# RF_Driver.net
KiCad netlist of a schematic drawn in Altium Designer
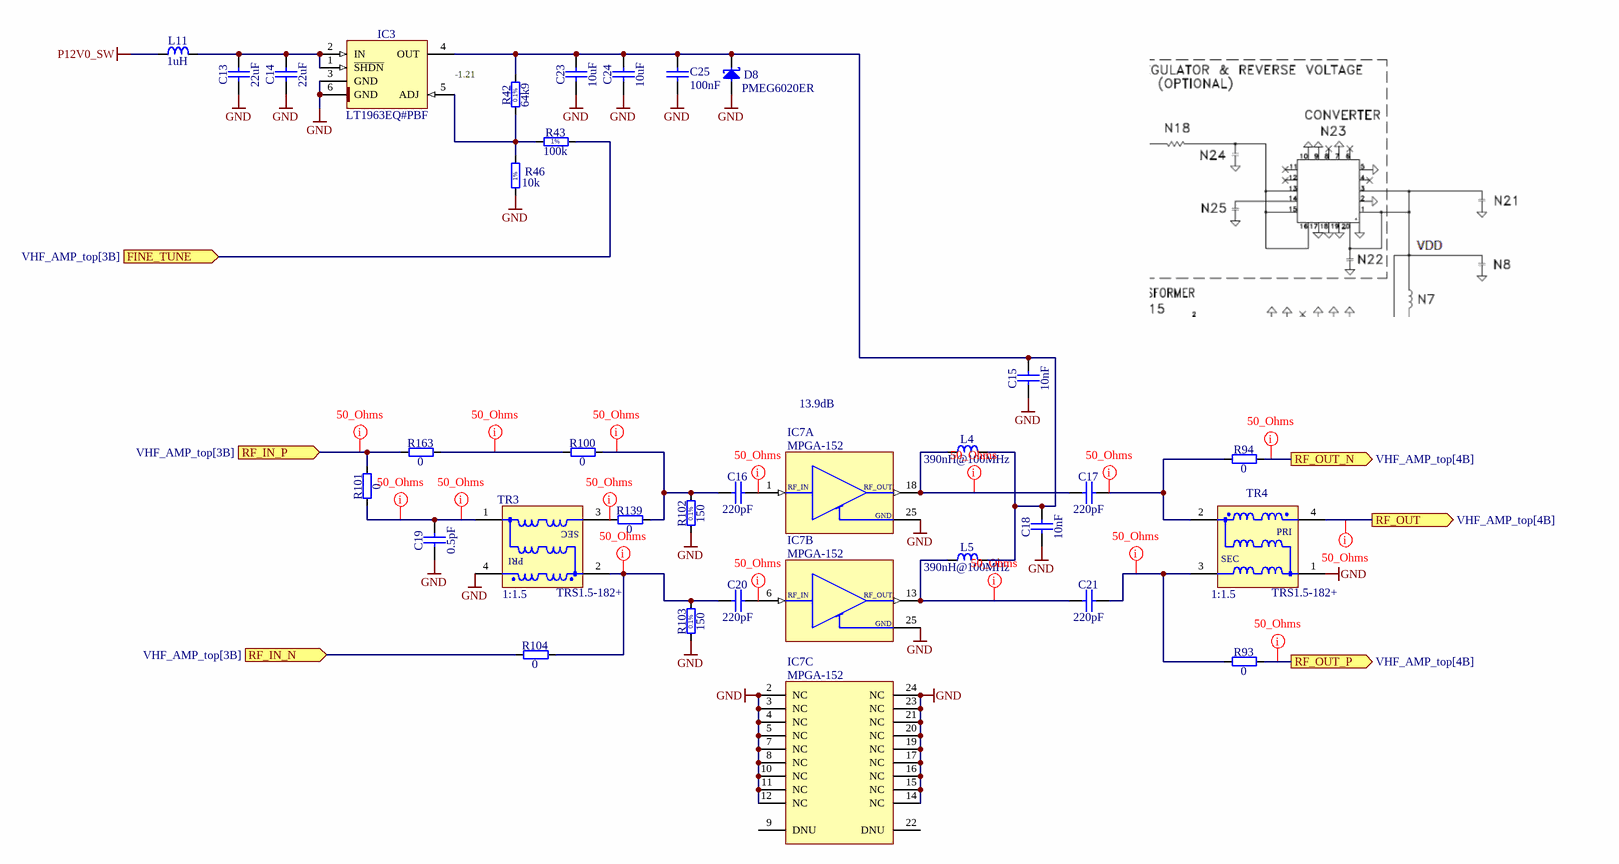
[diagram p0: RF_Driver.SchDoc]

(export (version "E")
  (design (tool "Eeschema 10.0.6"))
  (components
    (comp (ref "C13")
      (value "22uF")
      (footprint "CAPC3225X140N")
      (description "Non-polarised capacitor")
      (fields
        (field (name "PART NUMBER") "CC1210_22UF_25V_20%_X7R")
        (field (name "VOLTAGE") "25V")
        (field (name "AUTHOR") "CERN DEM JLC")
      )
      (libsource (lib "Capacitors") (part "Capacitor - non polarized"))
    )
    (comp (ref "C14")
      (value "22uF")
      (footprint "CAPC3225X140N")
      (description "Non-polarised capacitor")
      (fields
        (field (name "PART NUMBER") "CC1210_22UF_25V_20%_X7R")
        (field (name "VOLTAGE") "25V")
        (field (name "AUTHOR") "CERN DEM JLC")
      )
      (libsource (lib "Capacitors") (part "Capacitor - non polarized"))
    )
    (comp (ref "C15")
      (value "10nF")
      (footprint "CAPC1005X55N")
      (description "Non-polarised capacitor")
      (fields
        (field (name "PART NUMBER") "CC0402_10NF_16V_10%_X7R")
        (field (name "VOLTAGE") "16V")
        (field (name "AUTHOR") "CERN DEM JLC")
      )
      (libsource (lib "Capacitors") (part "Capacitor - non polarized"))
    )
    (comp (ref "C16")
      (value "220pF")
      (footprint "CAPC1005X55N")
      (description "Non-polarised capacitor")
      (fields
        (field (name "PART NUMBER") "CC0402_220PF_50V_5%_C0G")
        (field (name "VOLTAGE") "50V")
        (field (name "AUTHOR") "CERN DEM JLC")
      )
      (libsource (lib "Capacitors") (part "Capacitor - non polarized"))
    )
    (comp (ref "C17")
      (value "220pF")
      (footprint "CAPC1005X55N")
      (description "Non-polarised capacitor")
      (fields
        (field (name "PART NUMBER") "CC0402_220PF_50V_5%_C0G")
        (field (name "VOLTAGE") "50V")
        (field (name "AUTHOR") "CERN DEM JLC")
      )
      (libsource (lib "Capacitors") (part "Capacitor - non polarized"))
    )
    (comp (ref "C18")
      (value "10nF")
      (footprint "CAPC1005X55N")
      (description "Non-polarised capacitor")
      (fields
        (field (name "PART NUMBER") "CC0402_10NF_16V_10%_X7R")
        (field (name "VOLTAGE") "16V")
        (field (name "AUTHOR") "CERN DEM JLC")
      )
      (libsource (lib "Capacitors") (part "Capacitor - non polarized"))
    )
    (comp (ref "C19")
      (value "0.5pF")
      (footprint "CAPC1005X50N")
      (description "Non-polarised capacitor")
      (fields
        (field (name "PART NUMBER") "CC0402_0.5PF_25V_0.05PF_AVX_04023J0R5ABSTR")
        (field (name "VOLTAGE") "25V")
        (field (name "AUTHOR") "CERN DEM JLC")
      )
      (libsource (lib "Capacitors") (part "Capacitor - non polarized"))
    )
    (comp (ref "C20")
      (value "220pF")
      (footprint "CAPC1005X55N")
      (description "Non-polarised capacitor")
      (fields
        (field (name "PART NUMBER") "CC0402_220PF_50V_5%_C0G")
        (field (name "VOLTAGE") "50V")
        (field (name "AUTHOR") "CERN DEM JLC")
      )
      (libsource (lib "Capacitors") (part "Capacitor - non polarized"))
    )
    (comp (ref "C21")
      (value "220pF")
      (footprint "CAPC1005X55N")
      (description "Non-polarised capacitor")
      (fields
        (field (name "PART NUMBER") "CC0402_220PF_50V_5%_C0G")
        (field (name "VOLTAGE") "50V")
        (field (name "AUTHOR") "CERN DEM JLC")
      )
      (libsource (lib "Capacitors") (part "Capacitor - non polarized"))
    )
    (comp (ref "C23")
      (value "10uF")
      (footprint "CAPC3225X270N")
      (description "Non-polarised capacitor")
      (fields
        (field (name "PART NUMBER") "CC1210_10UF_25V_10%_X7R")
        (field (name "VOLTAGE") "25V")
        (field (name "AUTHOR") "CERN DEM JLC")
      )
      (libsource (lib "Capacitors") (part "Capacitor - non polarized"))
    )
    (comp (ref "C24")
      (value "10uF")
      (footprint "CAPC3225X270N")
      (description "Non-polarised capacitor")
      (fields
        (field (name "PART NUMBER") "CC1210_10UF_25V_10%_X7R")
        (field (name "VOLTAGE") "25V")
        (field (name "AUTHOR") "CERN DEM JLC")
      )
      (libsource (lib "Capacitors") (part "Capacitor - non polarized"))
    )
    (comp (ref "C25")
      (value "100nF")
      (footprint "CAPC1005X55N")
      (description "Non-polarised capacitor")
      (fields
        (field (name "PART NUMBER") "CC0402_100NF_16V_10%_X5R")
        (field (name "VOLTAGE") "16V")
        (field (name "AUTHOR") "CERN DEM JLC")
      )
      (libsource (lib "Capacitors") (part "Capacitor - non polarized"))
    )
    (comp (ref "D8")
      (value "PMEG6020ER")
      (footprint "SODFL3517X110N")
      (description "Schottky Diode")
      (fields
        (field (name "VOLTAGE") "60V")
        (field (name "POWER") "2A")
        (field (name "AUTHOR") "CERN DEM JMW")
      )
      (libsource (lib "ICs And Semiconductors") (part "Diode Schottky"))
    )
    (comp (ref "IC3")
      (value "LT1963EQ#PBF")
      (footprint "TO170P1394X457-6N-R900X1060")
      (description "1.5A, Fast Transient Response Adjustable LDO Regulators")
      (fields (field (name "MANUFACTURER") "LINEAR TECHNOLOGY") (field (name "AUTHOR") "CERN DEM JLC"))
      (libsource (lib "ICs And Semiconductors") (part "LT1963xQ"))
    )
    (comp (ref "IC7")
      (value "MPGA-152")
      (footprint "QFN50P400X400X100-25N-S265")
      (description "Dual Differential Inputs and  Complementary TTL outputs")
      (fields (field (name "MANUFACTURER") "MINI-CIRCUITS") (field (name "AUTHOR") "CERN DEM HF"))
      (libsource (lib "ICs And Semiconductors") (part "MPGA-152"))
    )
    (comp (ref "L4")
      (value "390nH@100MHz")
      (footprint "IND_COILCRAFT_0805HP")
      (description "Inductor")
      (fields
        (field (name "PART NUMBER") "IND0805_COILCRAFT_0805HP-391XGR")
        (field (name "POWER") "330mA")
        (field (name "AUTHOR") "CERN DEM JLC")
      )
      (libsource (lib "Inductors & Transformers") (part "Inductor"))
    )
    (comp (ref "L5")
      (value "390nH@100MHz")
      (footprint "IND_COILCRAFT_0805HP")
      (description "Inductor")
      (fields
        (field (name "PART NUMBER") "IND0805_COILCRAFT_0805HP-391XGR")
        (field (name "POWER") "330mA")
        (field (name "AUTHOR") "CERN DEM JLC")
      )
      (libsource (lib "Inductors & Transformers") (part "Inductor"))
    )
    (comp (ref "L11")
      (value "1uH")
      (footprint "INDC2620X100N")
      (description "Inductor")
      (fields
        (field (name "PART NUMBER") "IND1008_1UH_20%_WURTH_74479787210B")
        (field (name "POWER") "1.95A")
        (field (name "AUTHOR") "CERN DEM JLC")
      )
      (libsource (lib "Inductors & Transformers") (part "Inductor"))
    )
    (comp (ref "R42")
      (value "64k9")
      (footprint "RESC1608X55N")
      (description "Resistor - 0.1%")
      (fields
        (field (name "PART NUMBER") "R0603_64K9_0.1%_0.063W_10PPM")
        (field (name "POWER") "0.063W")
        (field (name "AUTHOR") "CERN DEM JLC")
      )
      (libsource (lib "Resistors") (part "Resistor - 0.1%"))
    )
    (comp (ref "R43")
      (value "100k")
      (footprint "RESC1608X55N")
      (description "Resistor - 1%")
      (fields
        (field (name "PART NUMBER") "R0603_100K_1%_0.1W_100PPM")
        (field (name "POWER") "0.1W")
        (field (name "AUTHOR") "CERN DEM JLC")
      )
      (libsource (lib "Resistors") (part "Resistor - 1%"))
    )
    (comp (ref "R46")
      (value "10k")
      (footprint "RESC1005X40N")
      (description "Resistor - 1%")
      (fields
        (field (name "PART NUMBER") "R0402_10K_1%_0.0625W_100PPM")
        (field (name "POWER") "0.0625W")
        (field (name "AUTHOR") "CERN DEM JLC")
      )
      (libsource (lib "Resistors") (part "Resistor - 1%"))
    )
    (comp (ref "R93")
      (value "0")
      (footprint "RESC2012X60N")
      (description "Resistor")
      (fields
        (field (name "PART NUMBER") "R0805_0R_JUMPER")
        (field (name "MANUFACTURER") "GENERIC")
        (field (name "AUTHOR") "CERN DEM JLC")
      )
      (libsource (lib "Resistors") (part "Resistor"))
    )
    (comp (ref "R94")
      (value "0")
      (footprint "RESC2012X60N")
      (description "Resistor")
      (fields
        (field (name "PART NUMBER") "R0805_0R_JUMPER")
        (field (name "MANUFACTURER") "GENERIC")
        (field (name "AUTHOR") "CERN DEM JLC")
      )
      (libsource (lib "Resistors") (part "Resistor"))
    )
    (comp (ref "R100")
      (value "0")
      (footprint "RESC2012X60N")
      (description "Resistor")
      (fields
        (field (name "PART NUMBER") "R0805_0R_JUMPER")
        (field (name "MANUFACTURER") "GENERIC")
        (field (name "AUTHOR") "CERN DEM JLC")
      )
      (libsource (lib "Resistors") (part "Resistor"))
    )
    (comp (ref "R101")
      (value "0")
      (footprint "RESC2012X60N")
      (description "Resistor")
      (fields
        (field (name "PART NUMBER") "R0805_0R_JUMPER")
        (field (name "MANUFACTURER") "GENERIC")
        (field (name "AUTHOR") "CERN DEM JLC")
      )
      (libsource (lib "Resistors") (part "Resistor"))
    )
    (comp (ref "R102")
      (value "150")
      (footprint "RESC1608X55N")
      (description "Resistor - 0.1%")
      (fields
        (field (name "PART NUMBER") "R0603_150R_0.1%_0.063W_10PPM")
        (field (name "POWER") "0.063W")
        (field (name "AUTHOR") "CERN DEM JLC")
      )
      (libsource (lib "Resistors") (part "Resistor - 0.1%"))
    )
    (comp (ref "R103")
      (value "150")
      (footprint "RESC1608X55N")
      (description "Resistor - 0.1%")
      (fields
        (field (name "PART NUMBER") "R0603_150R_0.1%_0.063W_10PPM")
        (field (name "POWER") "0.063W")
        (field (name "AUTHOR") "CERN DEM JLC")
      )
      (libsource (lib "Resistors") (part "Resistor - 0.1%"))
    )
    (comp (ref "R104")
      (value "0")
      (footprint "RESC2012X60N")
      (description "Resistor")
      (fields
        (field (name "PART NUMBER") "R0805_0R_JUMPER")
        (field (name "MANUFACTURER") "GENERIC")
        (field (name "AUTHOR") "CERN DEM JLC")
      )
      (libsource (lib "Resistors") (part "Resistor"))
    )
    (comp (ref "R139")
      (value "0")
      (footprint "RESC2012X60N")
      (description "Resistor")
      (fields
        (field (name "PART NUMBER") "R0805_0R_JUMPER")
        (field (name "MANUFACTURER") "GENERIC")
        (field (name "AUTHOR") "CERN DEM JLC")
      )
      (libsource (lib "Resistors") (part "Resistor"))
    )
    (comp (ref "R163")
      (value "0")
      (footprint "RESC2012X60N")
      (description "Resistor")
      (fields
        (field (name "PART NUMBER") "R0805_0R_JUMPER")
        (field (name "MANUFACTURER") "GENERIC")
        (field (name "AUTHOR") "CERN DEM JLC")
      )
      (libsource (lib "Resistors") (part "Resistor"))
    )
    (comp (ref "TR3")
      (value "1:1.5")
      (footprint "XFMR_MINI-CIRCUITS_TT1618")
      (description "50 Ohms 10 to 1800MHz RF Transformer")
      (fields
        (field (name "PART NUMBER") "XFMR_MINI-CIRCUITS_TRS1.5-182+")
        (field (name "POWER") "1W")
        (field (name "MANUFACTURER PART NUMBER") "TRS1.5-182+")
        (field (name "AUTHOR") "CERN DEM BC")
      )
      (libsource (lib "") (part "XFMR_MINI-CIRCUITS_TRS1.5-182+_1"))
    )
    (comp (ref "TR4")
      (value "1:1.5")
      (footprint "XFMR_MINI-CIRCUITS_TT1618")
      (description "50 Ohms 10 to 1800MHz RF Transformer")
      (fields
        (field (name "PART NUMBER") "XFMR_MINI-CIRCUITS_TRS1.5-182+")
        (field (name "POWER") "1W")
        (field (name "MANUFACTURER PART NUMBER") "TRS1.5-182+")
        (field (name "AUTHOR") "CERN DEM BC")
      )
      (libsource (lib "Inductors & Transformers") (part "XFMR_MINI-CIRCUITS_TRS1.5-182+"))
    )
  )
  (nets
    (net (code "1") (name "/FINE_TUNE") (class "Default")
      (node (ref "R43") (pin "2") (pinfunction "2_2") (pintype "passive"))
    )
    (net (code "2") (name "/RF_IN_N") (class "Default")
      (node (ref "R104") (pin "1") (pinfunction "1_1") (pintype "passive"))
    )
    (net (code "3") (name "/RF_IN_P") (class "Default")
      (node (ref "R101") (pin "2") (pinfunction "2_2") (pintype "passive"))
      (node (ref "R163") (pin "1") (pinfunction "1_1") (pintype "passive"))
    )
    (net (code "4") (name "/RF_OUT") (class "Default")
      (node (ref "TR4") (pin "4") (pinfunction "P1_4") (pintype "passive"))
    )
    (net (code "5") (name "/RF_OUT_N") (class "Default")
      (node (ref "R94") (pin "2") (pinfunction "2_2") (pintype "passive"))
    )
    (net (code "6") (name "/RF_OUT_P") (class "Default")
      (node (ref "R93") (pin "2") (pinfunction "2_2") (pintype "passive"))
    )
    (net (code "7") (name "GND") (class "Default")
      (node (ref "C13") (pin "1") (pinfunction "1_1") (pintype "passive"))
      (node (ref "C14") (pin "1") (pinfunction "1_1") (pintype "passive"))
      (node (ref "C15") (pin "1") (pinfunction "1_1") (pintype "passive"))
      (node (ref "C18") (pin "1") (pinfunction "1_1") (pintype "passive"))
      (node (ref "C19") (pin "1") (pinfunction "1_1") (pintype "passive"))
      (node (ref "C23") (pin "1") (pinfunction "1_1") (pintype "passive"))
      (node (ref "C24") (pin "1") (pinfunction "1_1") (pintype "passive"))
      (node (ref "C25") (pin "2") (pinfunction "2_2") (pintype "passive"))
      (node (ref "D8") (pin "2") (pinfunction "A_2") (pintype "passive"))
      (node (ref "IC3") (pin "3") (pinfunction "GND_3") (pintype "power_in"))
      (node (ref "IC3") (pin "6") (pinfunction "GND_6") (pintype "power_in"))
      (node (ref "IC7") (pin "10") (pinfunction "NC_10") (pintype "passive"))
      (node (ref "IC7") (pin "11") (pinfunction "NC_11") (pintype "passive"))
      (node (ref "IC7") (pin "12") (pinfunction "NC_12") (pintype "passive"))
      (node (ref "IC7") (pin "14") (pinfunction "NC_14") (pintype "passive"))
      (node (ref "IC7") (pin "15") (pinfunction "NC_15") (pintype "passive"))
      (node (ref "IC7") (pin "16") (pinfunction "NC_16") (pintype "passive"))
      (node (ref "IC7") (pin "17") (pinfunction "NC_17") (pintype "passive"))
      (node (ref "IC7") (pin "19") (pinfunction "NC_19") (pintype "passive"))
      (node (ref "IC7") (pin "2") (pinfunction "NC_2") (pintype "passive"))
      (node (ref "IC7") (pin "20") (pinfunction "NC_20") (pintype "passive"))
      (node (ref "IC7") (pin "21") (pinfunction "NC_21") (pintype "passive"))
      (node (ref "IC7") (pin "23") (pinfunction "NC_23") (pintype "passive"))
      (node (ref "IC7") (pin "24") (pinfunction "NC_24") (pintype "passive"))
      (node (ref "IC7") (pin "25") (pinfunction "GND_25") (pintype "power_in"))
      (node (ref "IC7") (pin "3") (pinfunction "NC_3") (pintype "passive"))
      (node (ref "IC7") (pin "4") (pinfunction "NC_4") (pintype "passive"))
      (node (ref "IC7") (pin "5") (pinfunction "NC_5") (pintype "passive"))
      (node (ref "IC7") (pin "7") (pinfunction "NC_7") (pintype "passive"))
      (node (ref "IC7") (pin "8") (pinfunction "NC_8") (pintype "passive"))
      (node (ref "R102") (pin "1") (pinfunction "1_1") (pintype "passive"))
      (node (ref "R103") (pin "1") (pinfunction "1_1") (pintype "passive"))
      (node (ref "R46") (pin "1") (pinfunction "1_1") (pintype "passive"))
      (node (ref "TR3") (pin "4") (pinfunction "P1_4") (pintype "passive"))
      (node (ref "TR4") (pin "1") (pinfunction "P1_1") (pintype "passive"))
    )
    (net (code "8") (name "Net-(C16-Pad1)") (class "Default")
      (node (ref "C16") (pin "1") (pinfunction "1_1") (pintype "passive"))
      (node (ref "R100") (pin "2") (pinfunction "2_2") (pintype "passive"))
      (node (ref "R102") (pin "2") (pinfunction "2_2") (pintype "passive"))
      (node (ref "R139") (pin "2") (pinfunction "2_2") (pintype "passive"))
    )
    (net (code "9") (name "Net-(C17-Pad2)") (class "Default")
      (node (ref "C17") (pin "2") (pinfunction "2_2") (pintype "passive"))
      (node (ref "R94") (pin "1") (pinfunction "1_1") (pintype "passive"))
      (node (ref "TR4") (pin "2") (pinfunction "S1_2") (pintype "passive"))
    )
    (net (code "10") (name "Net-(C19-Pad2)") (class "Default")
      (node (ref "C19") (pin "2") (pinfunction "2_2") (pintype "passive"))
      (node (ref "R101") (pin "1") (pinfunction "1_1") (pintype "passive"))
      (node (ref "TR3") (pin "1") (pinfunction "P1_1") (pintype "passive"))
    )
    (net (code "11") (name "Net-(C20-Pad1)") (class "Default")
      (node (ref "C20") (pin "1") (pinfunction "1_1") (pintype "passive"))
      (node (ref "R103") (pin "2") (pinfunction "2_2") (pintype "passive"))
      (node (ref "R104") (pin "2") (pinfunction "2_2") (pintype "passive"))
      (node (ref "TR3") (pin "2") (pinfunction "S1_2") (pintype "passive"))
    )
    (net (code "12") (name "Net-(C21-Pad2)") (class "Default")
      (node (ref "C21") (pin "2") (pinfunction "2_2") (pintype "passive"))
      (node (ref "R93") (pin "1") (pinfunction "1_1") (pintype "passive"))
      (node (ref "TR4") (pin "3") (pinfunction "S1_3") (pintype "passive"))
    )
    (net (code "13") (name "Net-(D8-C)") (class "Default")
      (node (ref "C15") (pin "2") (pinfunction "2_2") (pintype "passive"))
      (node (ref "C18") (pin "2") (pinfunction "2_2") (pintype "passive"))
      (node (ref "C23") (pin "2") (pinfunction "2_2") (pintype "passive"))
      (node (ref "C24") (pin "2") (pinfunction "2_2") (pintype "passive"))
      (node (ref "C25") (pin "1") (pinfunction "1_1") (pintype "passive"))
      (node (ref "D8") (pin "1") (pinfunction "C_1") (pintype "passive"))
      (node (ref "IC3") (pin "4") (pinfunction "OUT_4") (pintype "power_in"))
      (node (ref "L4") (pin "2") (pinfunction "2_2") (pintype "passive"))
      (node (ref "L5") (pin "2") (pinfunction "2_2") (pintype "passive"))
      (node (ref "R42") (pin "2") (pinfunction "2_2") (pintype "passive"))
    )
    (net (code "14") (name "Net-(IC3-ADJ)") (class "Default")
      (node (ref "IC3") (pin "5") (pinfunction "ADJ_5") (pintype "input"))
      (node (ref "R42") (pin "1") (pinfunction "1_1") (pintype "passive"))
      (node (ref "R43") (pin "1") (pinfunction "1_1") (pintype "passive"))
      (node (ref "R46") (pin "2") (pinfunction "2_2") (pintype "passive"))
    )
    (net (code "15") (name "Net-(IC3-IN)") (class "Default")
      (node (ref "C13") (pin "2") (pinfunction "2_2") (pintype "passive"))
      (node (ref "C14") (pin "2") (pinfunction "2_2") (pintype "passive"))
      (node (ref "IC3") (pin "1") (pinfunction "~{SHDN}_1") (pintype "input"))
      (node (ref "IC3") (pin "2") (pinfunction "IN_2") (pintype "input"))
      (node (ref "L11") (pin "2") (pinfunction "2_2") (pintype "passive"))
    )
    (net (code "16") (name "Net-(IC7A-RF-IN,_A1)") (class "Default")
      (node (ref "C16") (pin "2") (pinfunction "2_2") (pintype "passive"))
      (node (ref "IC7") (pin "1") (pinfunction "RF-IN,_A1_1") (pintype "input"))
    )
    (net (code "17") (name "Net-(IC7A-RF-OUT_and_DC-IN,_A1)") (class "Default")
      (node (ref "C17") (pin "1") (pinfunction "1_1") (pintype "passive"))
      (node (ref "IC7") (pin "18") (pinfunction "RF-OUT_and_DC-IN,_A1_18") (pintype "output"))
      (node (ref "L4") (pin "1") (pinfunction "1_1") (pintype "passive"))
    )
    (net (code "18") (name "Net-(IC7B-RF-OUT_and_DC-IN,_A2)") (class "Default")
      (node (ref "C21") (pin "1") (pinfunction "1_1") (pintype "passive"))
      (node (ref "IC7") (pin "13") (pinfunction "RF-OUT_and_DC-IN,_A2_13") (pintype "output"))
      (node (ref "L5") (pin "1") (pinfunction "1_1") (pintype "passive"))
    )
    (net (code "19") (name "Net-(IC7B-RF_IN,_A2)") (class "Default")
      (node (ref "C20") (pin "2") (pinfunction "2_2") (pintype "passive"))
      (node (ref "IC7") (pin "6") (pinfunction "RF_IN,_A2_6") (pintype "input"))
    )
    (net (code "20") (name "Net-(R100-Pad1)") (class "Default")
      (node (ref "R100") (pin "1") (pinfunction "1_1") (pintype "passive"))
      (node (ref "R163") (pin "2") (pinfunction "2_2") (pintype "passive"))
    )
    (net (code "21") (name "Net-(R139-Pad1)") (class "Default")
      (node (ref "R139") (pin "1") (pinfunction "1_1") (pintype "passive"))
      (node (ref "TR3") (pin "3") (pinfunction "S1_3") (pintype "passive"))
    )
    (net (code "22") (name "P12V0_SW") (class "Default")
      (node (ref "L11") (pin "1") (pinfunction "1_1") (pintype "passive"))
    )
    (net (code "23") (name "unconnected-(IC7C-DNU-Pad9)") (class "Default")
      (node (ref "IC7") (pin "9") (pinfunction "DNU_9") (pintype "passive"))
    )
    (net (code "24") (name "unconnected-(IC7C-DNU-Pad22)") (class "Default")
      (node (ref "IC7") (pin "22") (pinfunction "DNU_22") (pintype "passive"))
    )
  )
)
